# untitled5.net
KiCad netlist of a schematic drawn in EAGLE
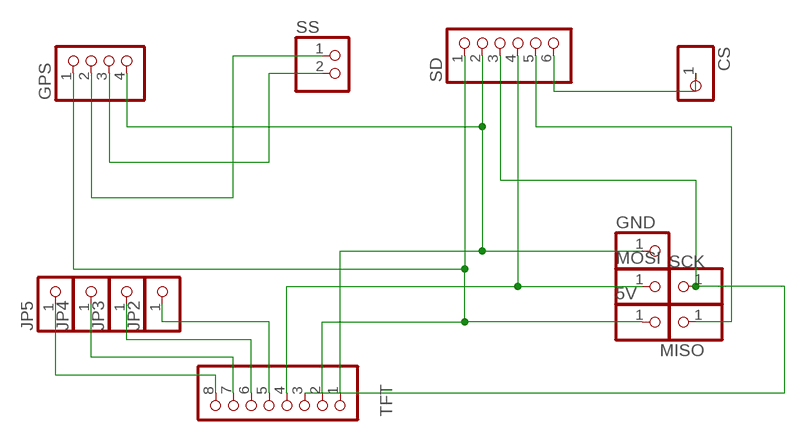
[diagram p0: schematic, sheet 1]

(export (version "E")
  (design (tool "Eeschema 10.0.6"))
  (components
    (comp (ref "5V")
      (value "PINHD-1X1")
      (footprint "eagle-import:1X01")
      (libsource (lib "eagle-import") (part "PINHD-1X1"))
    )
    (comp (ref "CS")
      (value "PINHD-1X1")
      (footprint "eagle-import:1X01")
      (libsource (lib "eagle-import") (part "PINHD-1X1"))
    )
    (comp (ref "GND")
      (value "PINHD-1X1")
      (footprint "eagle-import:1X01")
      (libsource (lib "eagle-import") (part "PINHD-1X1"))
    )
    (comp (ref "GPS")
      (value "PINHD-1X4")
      (footprint "eagle-import:1X04")
      (libsource (lib "eagle-import") (part "PINHD-1X4"))
    )
    (comp (ref "JP2")
      (value "PINHD-1X1")
      (footprint "eagle-import:1X01")
      (libsource (lib "eagle-import") (part "PINHD-1X1"))
    )
    (comp (ref "JP3")
      (value "PINHD-1X1")
      (footprint "eagle-import:1X01")
      (libsource (lib "eagle-import") (part "PINHD-1X1"))
    )
    (comp (ref "JP4")
      (value "PINHD-1X1")
      (footprint "eagle-import:1X01")
      (libsource (lib "eagle-import") (part "PINHD-1X1"))
    )
    (comp (ref "JP5")
      (value "PINHD-1X1")
      (footprint "eagle-import:1X01")
      (libsource (lib "eagle-import") (part "PINHD-1X1"))
    )
    (comp (ref "MISO")
      (value "PINHD-1X1")
      (footprint "eagle-import:1X01")
      (libsource (lib "eagle-import") (part "PINHD-1X1"))
    )
    (comp (ref "MOSI")
      (value "PINHD-1X1")
      (footprint "eagle-import:1X01")
      (libsource (lib "eagle-import") (part "PINHD-1X1"))
    )
    (comp (ref "SCK")
      (value "PINHD-1X1")
      (footprint "eagle-import:1X01")
      (libsource (lib "eagle-import") (part "PINHD-1X1"))
    )
    (comp (ref "SD")
      (value "PINHD-1X6")
      (footprint "eagle-import:1X06")
      (libsource (lib "eagle-import") (part "PINHD-1X6"))
    )
    (comp (ref "SS")
      (value "PINHD-1X2")
      (footprint "eagle-import:1X02")
      (libsource (lib "eagle-import") (part "PINHD-1X2"))
    )
    (comp (ref "TFT")
      (value "PINHD-1X8")
      (footprint "eagle-import:1X08")
      (libsource (lib "eagle-import") (part "PINHD-1X8"))
    )
  )
  (nets
    (net (code "1") (name "Net-(5V-Pad1)") (class "Default")
      (node (ref "5V") (pin "1") (pinfunction "1_1") (pintype "passive"))
      (node (ref "GPS") (pin "1") (pinfunction "1_1") (pintype "passive"))
      (node (ref "SD") (pin "1") (pinfunction "1_1") (pintype "passive"))
      (node (ref "TFT") (pin "2") (pinfunction "2_2") (pintype "passive"))
    )
    (net (code "2") (name "Net-(CS-Pad1)") (class "Default")
      (node (ref "CS") (pin "1") (pinfunction "1_1") (pintype "passive"))
      (node (ref "SD") (pin "6") (pinfunction "6_6") (pintype "passive"))
    )
    (net (code "3") (name "Net-(GND-Pad1)") (class "Default")
      (node (ref "GND") (pin "1") (pinfunction "1_1") (pintype "passive"))
      (node (ref "GPS") (pin "4") (pinfunction "4_4") (pintype "passive"))
      (node (ref "SD") (pin "2") (pinfunction "2_2") (pintype "passive"))
      (node (ref "TFT") (pin "1") (pinfunction "1_1") (pintype "passive"))
    )
    (net (code "4") (name "Net-(GPS-Pad2)") (class "Default")
      (node (ref "GPS") (pin "2") (pinfunction "2_2") (pintype "passive"))
      (node (ref "SS") (pin "1") (pinfunction "1_1") (pintype "passive"))
    )
    (net (code "5") (name "Net-(GPS-Pad3)") (class "Default")
      (node (ref "GPS") (pin "3") (pinfunction "3_3") (pintype "passive"))
      (node (ref "SS") (pin "2") (pinfunction "2_2") (pintype "passive"))
    )
    (net (code "6") (name "Net-(JP2-Pad1)") (class "Default")
      (node (ref "JP2") (pin "1") (pinfunction "1_1") (pintype "passive"))
      (node (ref "TFT") (pin "5") (pinfunction "5_5") (pintype "passive"))
    )
    (net (code "7") (name "Net-(JP3-Pad1)") (class "Default")
      (node (ref "JP3") (pin "1") (pinfunction "1_1") (pintype "passive"))
      (node (ref "TFT") (pin "6") (pinfunction "6_6") (pintype "passive"))
    )
    (net (code "8") (name "Net-(JP4-Pad1)") (class "Default")
      (node (ref "JP4") (pin "1") (pinfunction "1_1") (pintype "passive"))
      (node (ref "TFT") (pin "7") (pinfunction "7_7") (pintype "passive"))
    )
    (net (code "9") (name "Net-(JP5-Pad1)") (class "Default")
      (node (ref "JP5") (pin "1") (pinfunction "1_1") (pintype "passive"))
      (node (ref "TFT") (pin "8") (pinfunction "8_8") (pintype "passive"))
    )
    (net (code "10") (name "Net-(MISO-Pad1)") (class "Default")
      (node (ref "MISO") (pin "1") (pinfunction "1_1") (pintype "passive"))
      (node (ref "SD") (pin "5") (pinfunction "5_5") (pintype "passive"))
    )
    (net (code "11") (name "Net-(MOSI-Pad1)") (class "Default")
      (node (ref "MOSI") (pin "1") (pinfunction "1_1") (pintype "passive"))
      (node (ref "SD") (pin "4") (pinfunction "4_4") (pintype "passive"))
      (node (ref "TFT") (pin "4") (pinfunction "4_4") (pintype "passive"))
    )
    (net (code "12") (name "Net-(SCK-Pad1)") (class "Default")
      (node (ref "SCK") (pin "1") (pinfunction "1_1") (pintype "passive"))
      (node (ref "SD") (pin "3") (pinfunction "3_3") (pintype "passive"))
      (node (ref "TFT") (pin "3") (pinfunction "3_3") (pintype "passive"))
    )
  )
)
